# Stepper5.net
KiCad netlist of a schematic drawn in EAGLE
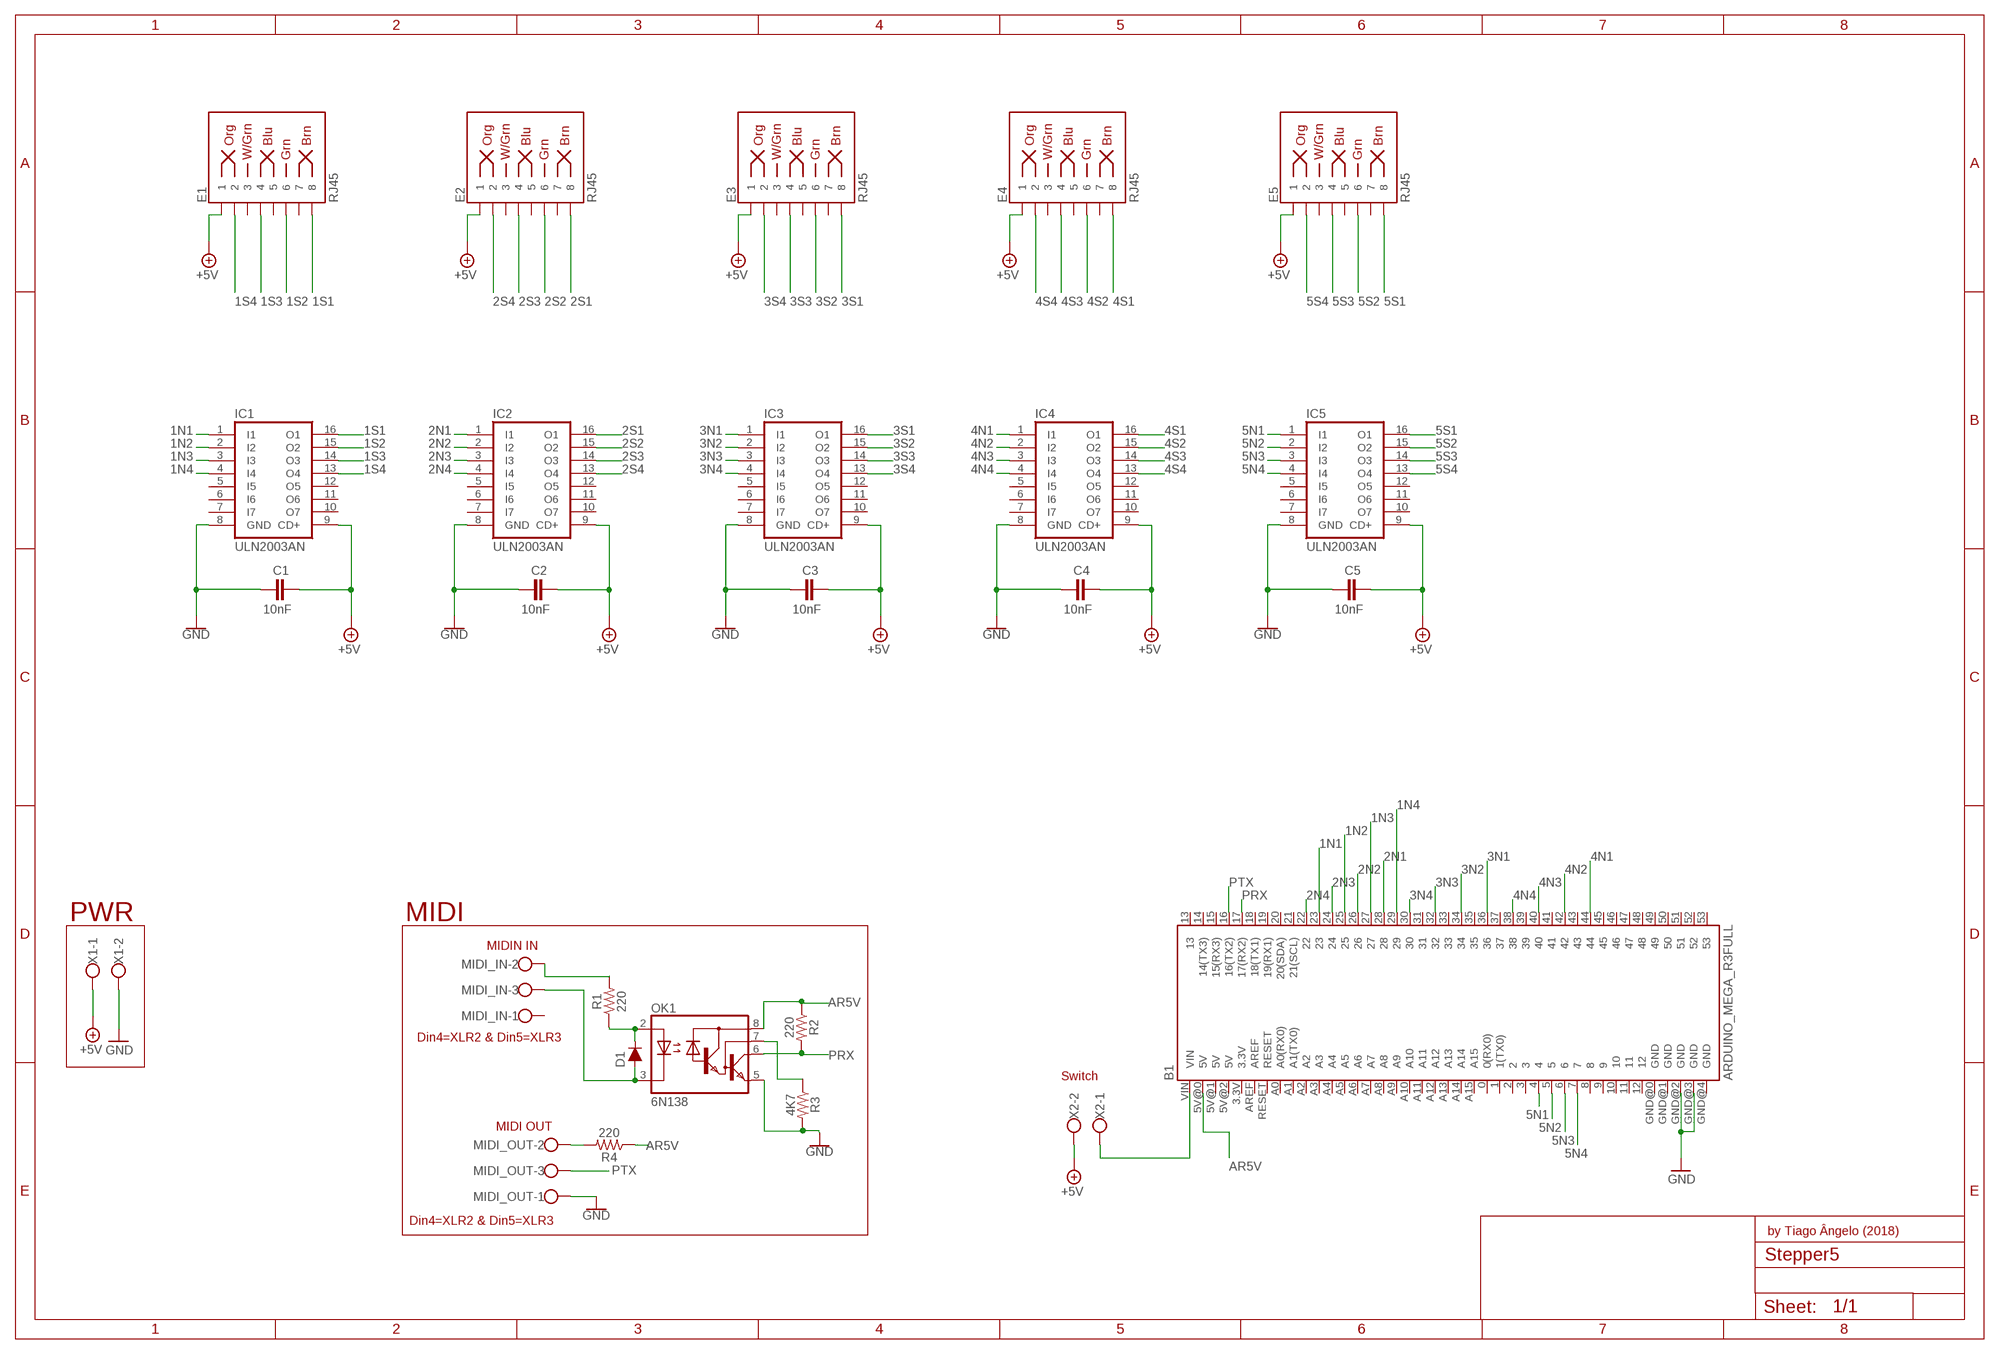
[diagram p0: schematic, sheet 1]

(export (version "E")
  (design (tool "Eeschema 10.0.6"))
  (components
    (comp (ref "B1")
      (value "ARDUINO_MEGA_R3FULL")
      (footprint "eagle-import:ARDUINO_MEGA")
      (libsource (lib "eagle-import") (part "ARDUINO_MEGA_R3FULL"))
    )
    (comp (ref "C1")
      (value "10nF")
      (footprint "eagle-import:C5B2.5")
      (libsource (lib "eagle-import") (part "C5/2.5"))
    )
    (comp (ref "C2")
      (value "10nF")
      (footprint "eagle-import:C5B2.5")
      (libsource (lib "eagle-import") (part "C5/2.5"))
    )
    (comp (ref "C3")
      (value "10nF")
      (footprint "eagle-import:C5B2.5")
      (libsource (lib "eagle-import") (part "C5/2.5"))
    )
    (comp (ref "C4")
      (value "10nF")
      (footprint "eagle-import:C5B2.5")
      (libsource (lib "eagle-import") (part "C5/2.5"))
    )
    (comp (ref "C5")
      (value "10nF")
      (footprint "eagle-import:C5B2.5")
      (libsource (lib "eagle-import") (part "C5/2.5"))
    )
    (comp (ref "D1")
      (value "200mA/100V/1V")
      (footprint "eagle-import:DIODE-1N4148")
      (libsource (lib "eagle-import") (part "DIODE-1N4148"))
    )
    (comp (ref "E1")
      (value "RJ45")
      (footprint "eagle-import:RJ45-8")
      (libsource (lib "eagle-import") (part "RJ45-8"))
    )
    (comp (ref "E2")
      (value "RJ45")
      (footprint "eagle-import:RJ45-8")
      (libsource (lib "eagle-import") (part "RJ45-8"))
    )
    (comp (ref "E3")
      (value "RJ45")
      (footprint "eagle-import:RJ45-8")
      (libsource (lib "eagle-import") (part "RJ45-8"))
    )
    (comp (ref "E4")
      (value "RJ45")
      (footprint "eagle-import:RJ45-8")
      (libsource (lib "eagle-import") (part "RJ45-8"))
    )
    (comp (ref "E5")
      (value "RJ45")
      (footprint "eagle-import:RJ45-8")
      (libsource (lib "eagle-import") (part "RJ45-8"))
    )
    (comp (ref "IC1")
      (value "ULN2003AN")
      (footprint "eagle-import:DIL16")
      (libsource (lib "eagle-import") (part "ULN2003AN"))
    )
    (comp (ref "IC2")
      (value "ULN2003AN")
      (footprint "eagle-import:DIL16")
      (libsource (lib "eagle-import") (part "ULN2003AN"))
    )
    (comp (ref "IC3")
      (value "ULN2003AN")
      (footprint "eagle-import:DIL16")
      (libsource (lib "eagle-import") (part "ULN2003AN"))
    )
    (comp (ref "IC4")
      (value "ULN2003AN")
      (footprint "eagle-import:DIL16")
      (libsource (lib "eagle-import") (part "ULN2003AN"))
    )
    (comp (ref "IC5")
      (value "ULN2003AN")
      (footprint "eagle-import:DIL16")
      (libsource (lib "eagle-import") (part "ULN2003AN"))
    )
    (comp (ref "MIDI_IN")
      (value "W237-103")
      (footprint "eagle-import:W237-103")
      (fields (field (name "MPN") "237-103"))
      (libsource (lib "eagle-import") (part "W237-103"))
    )
    (comp (ref "MIDI_OUT")
      (value "W237-103")
      (footprint "eagle-import:W237-103")
      (fields (field (name "MPN") "237-103"))
      (libsource (lib "eagle-import") (part "W237-103"))
    )
    (comp (ref "OK1")
      (value "6N138")
      (footprint "eagle-import:DIL08")
      (fields (field (name "MF") "VISHAY/TELEFUNKEN"))
      (libsource (lib "eagle-import") (part "6N138"))
    )
    (comp (ref "R1")
      (value "220")
      (footprint "eagle-import:AXIAL-0.3")
      (libsource (lib "eagle-import") (part "1KOHM-HORIZ-1/4W-5%"))
    )
    (comp (ref "R2")
      (value "220")
      (footprint "eagle-import:AXIAL-0.3")
      (libsource (lib "eagle-import") (part "1KOHM-HORIZ-1/4W-5%"))
    )
    (comp (ref "R3")
      (value "4K7")
      (footprint "eagle-import:AXIAL-0.3")
      (libsource (lib "eagle-import") (part "1KOHM-HORIZ-1/4W-5%"))
    )
    (comp (ref "R4")
      (value "220")
      (footprint "eagle-import:AXIAL-0.3")
      (libsource (lib "eagle-import") (part "1KOHM-HORIZ-1/4W-5%"))
    )
    (comp (ref "X1")
      (value "W237-102")
      (footprint "eagle-import:W237-102")
      (fields (field (name "MPN") "237-102"))
      (libsource (lib "eagle-import") (part "W237-102"))
    )
    (comp (ref "X2")
      (value "W237-102")
      (footprint "eagle-import:W237-102")
      (fields (field (name "MPN") "237-102"))
      (libsource (lib "eagle-import") (part "W237-102"))
    )
  )
  (nets
    (net (code "1") (name "+5V") (class "Default")
      (node (ref "C1") (pin "2") (pinfunction "2_2") (pintype "passive"))
      (node (ref "C2") (pin "2") (pinfunction "2_2") (pintype "passive"))
      (node (ref "C3") (pin "2") (pinfunction "2_2") (pintype "passive"))
      (node (ref "C4") (pin "2") (pinfunction "2_2") (pintype "passive"))
      (node (ref "C5") (pin "2") (pinfunction "2_2") (pintype "passive"))
      (node (ref "E1") (pin "1") (pinfunction "1_1") (pintype "bidirectional"))
      (node (ref "E2") (pin "1") (pinfunction "1_1") (pintype "bidirectional"))
      (node (ref "E3") (pin "1") (pinfunction "1_1") (pintype "bidirectional"))
      (node (ref "E4") (pin "1") (pinfunction "1_1") (pintype "bidirectional"))
      (node (ref "E5") (pin "1") (pinfunction "1_1") (pintype "bidirectional"))
      (node (ref "IC1") (pin "9") (pinfunction "CD+_9") (pintype "passive"))
      (node (ref "IC2") (pin "9") (pinfunction "CD+_9") (pintype "passive"))
      (node (ref "IC3") (pin "9") (pinfunction "CD+_9") (pintype "passive"))
      (node (ref "IC4") (pin "9") (pinfunction "CD+_9") (pintype "passive"))
      (node (ref "IC5") (pin "9") (pinfunction "CD+_9") (pintype "passive"))
      (node (ref "X1") (pin "1") (pinfunction "KL_1") (pintype "passive"))
      (node (ref "X2") (pin "2") (pinfunction "KL_2") (pintype "passive"))
    )
    (net (code "2") (name "/1N1") (class "Default")
      (node (ref "B1") (pin "23") (pinfunction "23_23") (pintype "bidirectional"))
      (node (ref "IC1") (pin "1") (pinfunction "I1_1") (pintype "input"))
    )
    (net (code "3") (name "/1N2") (class "Default")
      (node (ref "B1") (pin "25") (pinfunction "25_25") (pintype "bidirectional"))
      (node (ref "IC1") (pin "2") (pinfunction "I2_2") (pintype "input"))
    )
    (net (code "4") (name "/1N3") (class "Default")
      (node (ref "B1") (pin "27") (pinfunction "27_27") (pintype "bidirectional"))
      (node (ref "IC1") (pin "3") (pinfunction "I3_3") (pintype "input"))
    )
    (net (code "5") (name "/1N4") (class "Default")
      (node (ref "B1") (pin "29") (pinfunction "29_29") (pintype "bidirectional"))
      (node (ref "IC1") (pin "4") (pinfunction "I4_4") (pintype "input"))
    )
    (net (code "6") (name "/1S1") (class "Default")
      (node (ref "E1") (pin "8") (pinfunction "8_8") (pintype "bidirectional"))
      (node (ref "IC1") (pin "16") (pinfunction "O1_16") (pintype "open_collector"))
    )
    (net (code "7") (name "/1S2") (class "Default")
      (node (ref "E1") (pin "6") (pinfunction "6_6") (pintype "bidirectional"))
      (node (ref "IC1") (pin "15") (pinfunction "O2_15") (pintype "open_collector"))
    )
    (net (code "8") (name "/1S3") (class "Default")
      (node (ref "E1") (pin "4") (pinfunction "4_4") (pintype "bidirectional"))
      (node (ref "IC1") (pin "14") (pinfunction "O3_14") (pintype "open_collector"))
    )
    (net (code "9") (name "/1S4") (class "Default")
      (node (ref "E1") (pin "2") (pinfunction "2_2") (pintype "bidirectional"))
      (node (ref "IC1") (pin "13") (pinfunction "O4_13") (pintype "open_collector"))
    )
    (net (code "10") (name "/2N1") (class "Default")
      (node (ref "B1") (pin "28") (pinfunction "28_28") (pintype "bidirectional"))
      (node (ref "IC2") (pin "1") (pinfunction "I1_1") (pintype "input"))
    )
    (net (code "11") (name "/2N2") (class "Default")
      (node (ref "B1") (pin "26") (pinfunction "26_26") (pintype "bidirectional"))
      (node (ref "IC2") (pin "2") (pinfunction "I2_2") (pintype "input"))
    )
    (net (code "12") (name "/2N3") (class "Default")
      (node (ref "B1") (pin "24") (pinfunction "24_24") (pintype "bidirectional"))
      (node (ref "IC2") (pin "3") (pinfunction "I3_3") (pintype "input"))
    )
    (net (code "13") (name "/2N4") (class "Default")
      (node (ref "B1") (pin "22") (pinfunction "22_22") (pintype "bidirectional"))
      (node (ref "IC2") (pin "4") (pinfunction "I4_4") (pintype "input"))
    )
    (net (code "14") (name "/2S1") (class "Default")
      (node (ref "E2") (pin "8") (pinfunction "8_8") (pintype "bidirectional"))
      (node (ref "IC2") (pin "16") (pinfunction "O1_16") (pintype "open_collector"))
    )
    (net (code "15") (name "/2S2") (class "Default")
      (node (ref "E2") (pin "6") (pinfunction "6_6") (pintype "bidirectional"))
      (node (ref "IC2") (pin "15") (pinfunction "O2_15") (pintype "open_collector"))
    )
    (net (code "16") (name "/2S3") (class "Default")
      (node (ref "E2") (pin "4") (pinfunction "4_4") (pintype "bidirectional"))
      (node (ref "IC2") (pin "14") (pinfunction "O3_14") (pintype "open_collector"))
    )
    (net (code "17") (name "/2S4") (class "Default")
      (node (ref "E2") (pin "2") (pinfunction "2_2") (pintype "bidirectional"))
      (node (ref "IC2") (pin "13") (pinfunction "O4_13") (pintype "open_collector"))
    )
    (net (code "18") (name "/3N1") (class "Default")
      (node (ref "B1") (pin "36") (pinfunction "36_36") (pintype "bidirectional"))
      (node (ref "IC3") (pin "1") (pinfunction "I1_1") (pintype "input"))
    )
    (net (code "19") (name "/3N2") (class "Default")
      (node (ref "B1") (pin "34") (pinfunction "34_34") (pintype "bidirectional"))
      (node (ref "IC3") (pin "2") (pinfunction "I2_2") (pintype "input"))
    )
    (net (code "20") (name "/3N3") (class "Default")
      (node (ref "B1") (pin "32") (pinfunction "32_32") (pintype "bidirectional"))
      (node (ref "IC3") (pin "3") (pinfunction "I3_3") (pintype "input"))
    )
    (net (code "21") (name "/3N4") (class "Default")
      (node (ref "B1") (pin "30") (pinfunction "30_30") (pintype "bidirectional"))
      (node (ref "IC3") (pin "4") (pinfunction "I4_4") (pintype "input"))
    )
    (net (code "22") (name "/3S1") (class "Default")
      (node (ref "E3") (pin "8") (pinfunction "8_8") (pintype "bidirectional"))
      (node (ref "IC3") (pin "16") (pinfunction "O1_16") (pintype "open_collector"))
    )
    (net (code "23") (name "/3S2") (class "Default")
      (node (ref "E3") (pin "6") (pinfunction "6_6") (pintype "bidirectional"))
      (node (ref "IC3") (pin "15") (pinfunction "O2_15") (pintype "open_collector"))
    )
    (net (code "24") (name "/3S3") (class "Default")
      (node (ref "E3") (pin "4") (pinfunction "4_4") (pintype "bidirectional"))
      (node (ref "IC3") (pin "14") (pinfunction "O3_14") (pintype "open_collector"))
    )
    (net (code "25") (name "/3S4") (class "Default")
      (node (ref "E3") (pin "2") (pinfunction "2_2") (pintype "bidirectional"))
      (node (ref "IC3") (pin "13") (pinfunction "O4_13") (pintype "open_collector"))
    )
    (net (code "26") (name "/4N1") (class "Default")
      (node (ref "B1") (pin "44") (pinfunction "44_44") (pintype "bidirectional"))
      (node (ref "IC4") (pin "1") (pinfunction "I1_1") (pintype "input"))
    )
    (net (code "27") (name "/4N2") (class "Default")
      (node (ref "B1") (pin "42") (pinfunction "42_42") (pintype "bidirectional"))
      (node (ref "IC4") (pin "2") (pinfunction "I2_2") (pintype "input"))
    )
    (net (code "28") (name "/4N3") (class "Default")
      (node (ref "B1") (pin "40") (pinfunction "40_40") (pintype "bidirectional"))
      (node (ref "IC4") (pin "3") (pinfunction "I3_3") (pintype "input"))
    )
    (net (code "29") (name "/4N4") (class "Default")
      (node (ref "B1") (pin "38") (pinfunction "38_38") (pintype "bidirectional"))
      (node (ref "IC4") (pin "4") (pinfunction "I4_4") (pintype "input"))
    )
    (net (code "30") (name "/4S1") (class "Default")
      (node (ref "E4") (pin "8") (pinfunction "8_8") (pintype "bidirectional"))
      (node (ref "IC4") (pin "16") (pinfunction "O1_16") (pintype "open_collector"))
    )
    (net (code "31") (name "/4S2") (class "Default")
      (node (ref "E4") (pin "6") (pinfunction "6_6") (pintype "bidirectional"))
      (node (ref "IC4") (pin "15") (pinfunction "O2_15") (pintype "open_collector"))
    )
    (net (code "32") (name "/4S3") (class "Default")
      (node (ref "E4") (pin "4") (pinfunction "4_4") (pintype "bidirectional"))
      (node (ref "IC4") (pin "14") (pinfunction "O3_14") (pintype "open_collector"))
    )
    (net (code "33") (name "/4S4") (class "Default")
      (node (ref "E4") (pin "2") (pinfunction "2_2") (pintype "bidirectional"))
      (node (ref "IC4") (pin "13") (pinfunction "O4_13") (pintype "open_collector"))
    )
    (net (code "34") (name "/5N1") (class "Default")
      (node (ref "B1") (pin "4") (pinfunction "4_4") (pintype "bidirectional"))
      (node (ref "IC5") (pin "1") (pinfunction "I1_1") (pintype "input"))
    )
    (net (code "35") (name "/5N2") (class "Default")
      (node (ref "B1") (pin "5") (pinfunction "5_5") (pintype "bidirectional"))
      (node (ref "IC5") (pin "2") (pinfunction "I2_2") (pintype "input"))
    )
    (net (code "36") (name "/5N3") (class "Default")
      (node (ref "B1") (pin "6") (pinfunction "6_6") (pintype "bidirectional"))
      (node (ref "IC5") (pin "3") (pinfunction "I3_3") (pintype "input"))
    )
    (net (code "37") (name "/5N4") (class "Default")
      (node (ref "B1") (pin "7") (pinfunction "7_7") (pintype "bidirectional"))
      (node (ref "IC5") (pin "4") (pinfunction "I4_4") (pintype "input"))
    )
    (net (code "38") (name "/5S1") (class "Default")
      (node (ref "E5") (pin "8") (pinfunction "8_8") (pintype "bidirectional"))
      (node (ref "IC5") (pin "16") (pinfunction "O1_16") (pintype "open_collector"))
    )
    (net (code "39") (name "/5S2") (class "Default")
      (node (ref "E5") (pin "6") (pinfunction "6_6") (pintype "bidirectional"))
      (node (ref "IC5") (pin "15") (pinfunction "O2_15") (pintype "open_collector"))
    )
    (net (code "40") (name "/5S3") (class "Default")
      (node (ref "E5") (pin "4") (pinfunction "4_4") (pintype "bidirectional"))
      (node (ref "IC5") (pin "14") (pinfunction "O3_14") (pintype "open_collector"))
    )
    (net (code "41") (name "/5S4") (class "Default")
      (node (ref "E5") (pin "2") (pinfunction "2_2") (pintype "bidirectional"))
      (node (ref "IC5") (pin "13") (pinfunction "O4_13") (pintype "open_collector"))
    )
    (net (code "42") (name "/AR5V") (class "Default")
      (node (ref "B1") (pin "5V@0") (pinfunction "5V_5V@0") (pintype "bidirectional"))
      (node (ref "OK1") (pin "8") (pinfunction "VCC_8") (pintype "passive"))
      (node (ref "R2") (pin "P$1") (pinfunction "1_P$1") (pintype "passive"))
      (node (ref "R4") (pin "P$1") (pinfunction "1_P$1") (pintype "passive"))
    )
    (net (code "43") (name "/PRX") (class "Default")
      (node (ref "B1") (pin "17") (pinfunction "17(RX2)_17") (pintype "bidirectional"))
      (node (ref "OK1") (pin "6") (pinfunction "VO_6") (pintype "passive"))
      (node (ref "R2") (pin "P$2") (pinfunction "2_P$2") (pintype "passive"))
    )
    (net (code "44") (name "/PTX") (class "Default")
      (node (ref "B1") (pin "16") (pinfunction "16(TX2)_16") (pintype "bidirectional"))
      (node (ref "MIDI_OUT") (pin "3") (pinfunction "KL_3") (pintype "passive"))
    )
    (net (code "45") (name "GND") (class "Default")
      (node (ref "B1") (pin "GND@2") (pinfunction "GND_GND@2") (pintype "bidirectional"))
      (node (ref "B1") (pin "GND@3") (pinfunction "GND_GND@3") (pintype "bidirectional"))
      (node (ref "C1") (pin "1") (pinfunction "1_1") (pintype "passive"))
      (node (ref "C2") (pin "1") (pinfunction "1_1") (pintype "passive"))
      (node (ref "C3") (pin "1") (pinfunction "1_1") (pintype "passive"))
      (node (ref "C4") (pin "1") (pinfunction "1_1") (pintype "passive"))
      (node (ref "C5") (pin "1") (pinfunction "1_1") (pintype "passive"))
      (node (ref "IC1") (pin "8") (pinfunction "GND_8") (pintype "power_in"))
      (node (ref "IC2") (pin "8") (pinfunction "GND_8") (pintype "power_in"))
      (node (ref "IC3") (pin "8") (pinfunction "GND_8") (pintype "power_in"))
      (node (ref "IC4") (pin "8") (pinfunction "GND_8") (pintype "power_in"))
      (node (ref "IC5") (pin "8") (pinfunction "GND_8") (pintype "power_in"))
      (node (ref "MIDI_OUT") (pin "1") (pinfunction "KL_1") (pintype "passive"))
      (node (ref "OK1") (pin "5") (pinfunction "GND_5") (pintype "passive"))
      (node (ref "R3") (pin "P$2") (pinfunction "2_P$2") (pintype "passive"))
      (node (ref "X1") (pin "2") (pinfunction "KL_2") (pintype "passive"))
    )
    (net (code "46") (name "Net-(MIDI_INB-KL)") (class "Default")
      (node (ref "MIDI_IN") (pin "2") (pinfunction "KL_2") (pintype "passive"))
      (node (ref "R1") (pin "P$2") (pinfunction "2_P$2") (pintype "passive"))
    )
    (net (code "47") (name "Net-(MIDI_INC-KL)") (class "Default")
      (node (ref "D1") (pin "A") (pinfunction "A_A") (pintype "passive"))
      (node (ref "MIDI_IN") (pin "3") (pinfunction "KL_3") (pintype "passive"))
      (node (ref "OK1") (pin "3") (pinfunction "C_3") (pintype "passive"))
    )
    (net (code "48") (name "Net-(MIDI_OUTB-KL)") (class "Default")
      (node (ref "MIDI_OUT") (pin "2") (pinfunction "KL_2") (pintype "passive"))
      (node (ref "R4") (pin "P$2") (pinfunction "2_P$2") (pintype "passive"))
    )
    (net (code "49") (name "Net-(OK1-A)") (class "Default")
      (node (ref "D1") (pin "C") (pinfunction "C_C") (pintype "passive"))
      (node (ref "OK1") (pin "2") (pinfunction "A_2") (pintype "passive"))
      (node (ref "R1") (pin "P$1") (pinfunction "1_P$1") (pintype "passive"))
    )
    (net (code "50") (name "Net-(OK1-VB)") (class "Default")
      (node (ref "OK1") (pin "7") (pinfunction "VB_7") (pintype "passive"))
      (node (ref "R3") (pin "P$1") (pinfunction "1_P$1") (pintype "passive"))
    )
    (net (code "51") (name "Net-(X2A-KL)") (class "Default")
      (node (ref "B1") (pin "VIN") (pinfunction "VIN_VIN") (pintype "bidirectional"))
      (node (ref "X2") (pin "1") (pinfunction "KL_1") (pintype "passive"))
    )
    (net (code "52") (name "unconnected-(B1-0(RX0)-Pad0)") (class "Default")
      (node (ref "B1") (pin "0") (pinfunction "0(RX0)_0") (pintype "bidirectional"))
    )
    (net (code "53") (name "unconnected-(B1-1(TX0)-Pad1)") (class "Default")
      (node (ref "B1") (pin "1") (pinfunction "1(TX0)_1") (pintype "bidirectional"))
    )
    (net (code "54") (name "unconnected-(B1-5V-Pad5V@1)") (class "Default")
      (node (ref "B1") (pin "5V@1") (pinfunction "5V_5V@1") (pintype "bidirectional"))
    )
    (net (code "55") (name "unconnected-(B1-5V-Pad5V@2)") (class "Default")
      (node (ref "B1") (pin "5V@2") (pinfunction "5V_5V@2") (pintype "bidirectional"))
    )
    (net (code "56") (name "unconnected-(B1-14(TX3)-Pad14)") (class "Default")
      (node (ref "B1") (pin "14") (pinfunction "14(TX3)_14") (pintype "bidirectional"))
    )
    (net (code "57") (name "unconnected-(B1-15(RX3)-Pad15)") (class "Default")
      (node (ref "B1") (pin "15") (pinfunction "15(RX3)_15") (pintype "bidirectional"))
    )
    (net (code "58") (name "unconnected-(B1-18(TX1)-Pad18)") (class "Default")
      (node (ref "B1") (pin "18") (pinfunction "18(TX1)_18") (pintype "bidirectional"))
    )
    (net (code "59") (name "unconnected-(B1-19(RX1)-Pad19)") (class "Default")
      (node (ref "B1") (pin "19") (pinfunction "19(RX1)_19") (pintype "bidirectional"))
    )
    (net (code "60") (name "unconnected-(B1-20(SDA)-Pad20)") (class "Default")
      (node (ref "B1") (pin "20") (pinfunction "20(SDA)_20") (pintype "bidirectional"))
    )
    (net (code "61") (name "unconnected-(B1-21(SCL)-Pad21)") (class "Default")
      (node (ref "B1") (pin "21") (pinfunction "21(SCL)_21") (pintype "bidirectional"))
    )
    (net (code "62") (name "unconnected-(B1-A0(RX0)-PadA0)") (class "Default")
      (node (ref "B1") (pin "A0") (pinfunction "A0(RX0)_A0") (pintype "bidirectional"))
    )
    (net (code "63") (name "unconnected-(B1-A1(TX0)-PadA1)") (class "Default")
      (node (ref "B1") (pin "A1") (pinfunction "A1(TX0)_A1") (pintype "bidirectional"))
    )
    (net (code "64") (name "unconnected-(B1-GND-PadGND@0)") (class "Default")
      (node (ref "B1") (pin "GND@0") (pinfunction "GND_GND@0") (pintype "bidirectional"))
    )
    (net (code "65") (name "unconnected-(B1-GND-PadGND@1)") (class "Default")
      (node (ref "B1") (pin "GND@1") (pinfunction "GND_GND@1") (pintype "bidirectional"))
    )
    (net (code "66") (name "unconnected-(B1-GND-PadGND@4)") (class "Default")
      (node (ref "B1") (pin "GND@4") (pinfunction "GND_GND@4") (pintype "bidirectional"))
    )
    (net (code "67") (name "unconnected-(B1-Pad2)") (class "Default")
      (node (ref "B1") (pin "2") (pinfunction "2_2") (pintype "bidirectional"))
    )
    (net (code "68") (name "unconnected-(B1-Pad3)") (class "Default")
      (node (ref "B1") (pin "3") (pinfunction "3_3") (pintype "bidirectional"))
    )
    (net (code "69") (name "unconnected-(B1-Pad3.3V)") (class "Default")
      (node (ref "B1") (pin "3.3V") (pinfunction "3.3V_3.3V") (pintype "bidirectional"))
    )
    (net (code "70") (name "unconnected-(B1-Pad8)") (class "Default")
      (node (ref "B1") (pin "8") (pinfunction "8_8") (pintype "bidirectional"))
    )
    (net (code "71") (name "unconnected-(B1-Pad9)") (class "Default")
      (node (ref "B1") (pin "9") (pinfunction "9_9") (pintype "bidirectional"))
    )
    (net (code "72") (name "unconnected-(B1-Pad10)") (class "Default")
      (node (ref "B1") (pin "10") (pinfunction "10_10") (pintype "bidirectional"))
    )
    (net (code "73") (name "unconnected-(B1-Pad11)") (class "Default")
      (node (ref "B1") (pin "11") (pinfunction "11_11") (pintype "bidirectional"))
    )
    (net (code "74") (name "unconnected-(B1-Pad12)") (class "Default")
      (node (ref "B1") (pin "12") (pinfunction "12_12") (pintype "bidirectional"))
    )
    (net (code "75") (name "unconnected-(B1-Pad13)") (class "Default")
      (node (ref "B1") (pin "13") (pinfunction "13_13") (pintype "bidirectional"))
    )
    (net (code "76") (name "unconnected-(B1-Pad31)") (class "Default")
      (node (ref "B1") (pin "31") (pinfunction "31_31") (pintype "bidirectional"))
    )
    (net (code "77") (name "unconnected-(B1-Pad33)") (class "Default")
      (node (ref "B1") (pin "33") (pinfunction "33_33") (pintype "bidirectional"))
    )
    (net (code "78") (name "unconnected-(B1-Pad35)") (class "Default")
      (node (ref "B1") (pin "35") (pinfunction "35_35") (pintype "bidirectional"))
    )
    (net (code "79") (name "unconnected-(B1-Pad37)") (class "Default")
      (node (ref "B1") (pin "37") (pinfunction "37_37") (pintype "bidirectional"))
    )
    (net (code "80") (name "unconnected-(B1-Pad39)") (class "Default")
      (node (ref "B1") (pin "39") (pinfunction "39_39") (pintype "bidirectional"))
    )
    (net (code "81") (name "unconnected-(B1-Pad41)") (class "Default")
      (node (ref "B1") (pin "41") (pinfunction "41_41") (pintype "bidirectional"))
    )
    (net (code "82") (name "unconnected-(B1-Pad43)") (class "Default")
      (node (ref "B1") (pin "43") (pinfunction "43_43") (pintype "bidirectional"))
    )
    (net (code "83") (name "unconnected-(B1-Pad45)") (class "Default")
      (node (ref "B1") (pin "45") (pinfunction "45_45") (pintype "bidirectional"))
    )
    (net (code "84") (name "unconnected-(B1-Pad46)") (class "Default")
      (node (ref "B1") (pin "46") (pinfunction "46_46") (pintype "bidirectional"))
    )
    (net (code "85") (name "unconnected-(B1-Pad47)") (class "Default")
      (node (ref "B1") (pin "47") (pinfunction "47_47") (pintype "bidirectional"))
    )
    (net (code "86") (name "unconnected-(B1-Pad48)") (class "Default")
      (node (ref "B1") (pin "48") (pinfunction "48_48") (pintype "bidirectional"))
    )
    (net (code "87") (name "unconnected-(B1-Pad49)") (class "Default")
      (node (ref "B1") (pin "49") (pinfunction "49_49") (pintype "bidirectional"))
    )
    (net (code "88") (name "unconnected-(B1-Pad50)") (class "Default")
      (node (ref "B1") (pin "50") (pinfunction "50_50") (pintype "bidirectional"))
    )
    (net (code "89") (name "unconnected-(B1-Pad51)") (class "Default")
      (node (ref "B1") (pin "51") (pinfunction "51_51") (pintype "bidirectional"))
    )
    (net (code "90") (name "unconnected-(B1-Pad52)") (class "Default")
      (node (ref "B1") (pin "52") (pinfunction "52_52") (pintype "bidirectional"))
    )
    (net (code "91") (name "unconnected-(B1-Pad53)") (class "Default")
      (node (ref "B1") (pin "53") (pinfunction "53_53") (pintype "bidirectional"))
    )
    (net (code "92") (name "unconnected-(B1-PadA2)") (class "Default")
      (node (ref "B1") (pin "A2") (pinfunction "A2_A2") (pintype "bidirectional"))
    )
    (net (code "93") (name "unconnected-(B1-PadA3)") (class "Default")
      (node (ref "B1") (pin "A3") (pinfunction "A3_A3") (pintype "bidirectional"))
    )
    (net (code "94") (name "unconnected-(B1-PadA4)") (class "Default")
      (node (ref "B1") (pin "A4") (pinfunction "A4_A4") (pintype "bidirectional"))
    )
    (net (code "95") (name "unconnected-(B1-PadA5)") (class "Default")
      (node (ref "B1") (pin "A5") (pinfunction "A5_A5") (pintype "bidirectional"))
    )
    (net (code "96") (name "unconnected-(B1-PadA6)") (class "Default")
      (node (ref "B1") (pin "A6") (pinfunction "A6_A6") (pintype "bidirectional"))
    )
    (net (code "97") (name "unconnected-(B1-PadA7)") (class "Default")
      (node (ref "B1") (pin "A7") (pinfunction "A7_A7") (pintype "bidirectional"))
    )
    (net (code "98") (name "unconnected-(B1-PadA8)") (class "Default")
      (node (ref "B1") (pin "A8") (pinfunction "A8_A8") (pintype "bidirectional"))
    )
    (net (code "99") (name "unconnected-(B1-PadA9)") (class "Default")
      (node (ref "B1") (pin "A9") (pinfunction "A9_A9") (pintype "bidirectional"))
    )
    (net (code "100") (name "unconnected-(B1-PadA10)") (class "Default")
      (node (ref "B1") (pin "A10") (pinfunction "A10_A10") (pintype "bidirectional"))
    )
    (net (code "101") (name "unconnected-(B1-PadA11)") (class "Default")
      (node (ref "B1") (pin "A11") (pinfunction "A11_A11") (pintype "bidirectional"))
    )
    (net (code "102") (name "unconnected-(B1-PadA12)") (class "Default")
      (node (ref "B1") (pin "A12") (pinfunction "A12_A12") (pintype "bidirectional"))
    )
    (net (code "103") (name "unconnected-(B1-PadA13)") (class "Default")
      (node (ref "B1") (pin "A13") (pinfunction "A13_A13") (pintype "bidirectional"))
    )
    (net (code "104") (name "unconnected-(B1-PadA14)") (class "Default")
      (node (ref "B1") (pin "A14") (pinfunction "A14_A14") (pintype "bidirectional"))
    )
    (net (code "105") (name "unconnected-(B1-PadA15)") (class "Default")
      (node (ref "B1") (pin "A15") (pinfunction "A15_A15") (pintype "bidirectional"))
    )
    (net (code "106") (name "unconnected-(B1-PadAREF)") (class "Default")
      (node (ref "B1") (pin "AREF") (pinfunction "AREF_AREF") (pintype "bidirectional"))
    )
    (net (code "107") (name "unconnected-(B1-PadRESET)") (class "Default")
      (node (ref "B1") (pin "RESET") (pinfunction "RESET_RESET") (pintype "bidirectional"))
    )
    (net (code "108") (name "unconnected-(E1-Pad3)") (class "Default")
      (node (ref "E1") (pin "3") (pinfunction "3_3") (pintype "bidirectional"))
    )
    (net (code "109") (name "unconnected-(E1-Pad5)") (class "Default")
      (node (ref "E1") (pin "5") (pinfunction "5_5") (pintype "bidirectional"))
    )
    (net (code "110") (name "unconnected-(E1-Pad7)") (class "Default")
      (node (ref "E1") (pin "7") (pinfunction "7_7") (pintype "bidirectional"))
    )
    (net (code "111") (name "unconnected-(E2-Pad3)") (class "Default")
      (node (ref "E2") (pin "3") (pinfunction "3_3") (pintype "bidirectional"))
    )
    (net (code "112") (name "unconnected-(E2-Pad5)") (class "Default")
      (node (ref "E2") (pin "5") (pinfunction "5_5") (pintype "bidirectional"))
    )
    (net (code "113") (name "unconnected-(E2-Pad7)") (class "Default")
      (node (ref "E2") (pin "7") (pinfunction "7_7") (pintype "bidirectional"))
    )
    (net (code "114") (name "unconnected-(E3-Pad3)") (class "Default")
      (node (ref "E3") (pin "3") (pinfunction "3_3") (pintype "bidirectional"))
    )
    (net (code "115") (name "unconnected-(E3-Pad5)") (class "Default")
      (node (ref "E3") (pin "5") (pinfunction "5_5") (pintype "bidirectional"))
    )
    (net (code "116") (name "unconnected-(E3-Pad7)") (class "Default")
      (node (ref "E3") (pin "7") (pinfunction "7_7") (pintype "bidirectional"))
    )
    (net (code "117") (name "unconnected-(E4-Pad3)") (class "Default")
      (node (ref "E4") (pin "3") (pinfunction "3_3") (pintype "bidirectional"))
    )
    (net (code "118") (name "unconnected-(E4-Pad5)") (class "Default")
      (node (ref "E4") (pin "5") (pinfunction "5_5") (pintype "bidirectional"))
    )
    (net (code "119") (name "unconnected-(E4-Pad7)") (class "Default")
      (node (ref "E4") (pin "7") (pinfunction "7_7") (pintype "bidirectional"))
    )
    (net (code "120") (name "unconnected-(E5-Pad3)") (class "Default")
      (node (ref "E5") (pin "3") (pinfunction "3_3") (pintype "bidirectional"))
    )
    (net (code "121") (name "unconnected-(E5-Pad5)") (class "Default")
      (node (ref "E5") (pin "5") (pinfunction "5_5") (pintype "bidirectional"))
    )
    (net (code "122") (name "unconnected-(E5-Pad7)") (class "Default")
      (node (ref "E5") (pin "7") (pinfunction "7_7") (pintype "bidirectional"))
    )
    (net (code "123") (name "unconnected-(IC1-I5-Pad5)") (class "Default")
      (node (ref "IC1") (pin "5") (pinfunction "I5_5") (pintype "input"))
    )
    (net (code "124") (name "unconnected-(IC1-I6-Pad6)") (class "Default")
      (node (ref "IC1") (pin "6") (pinfunction "I6_6") (pintype "input"))
    )
    (net (code "125") (name "unconnected-(IC1-I7-Pad7)") (class "Default")
      (node (ref "IC1") (pin "7") (pinfunction "I7_7") (pintype "input"))
    )
    (net (code "126") (name "unconnected-(IC1-O5-Pad12)") (class "Default")
      (node (ref "IC1") (pin "12") (pinfunction "O5_12") (pintype "open_collector"))
    )
    (net (code "127") (name "unconnected-(IC1-O6-Pad11)") (class "Default")
      (node (ref "IC1") (pin "11") (pinfunction "O6_11") (pintype "open_collector"))
    )
    (net (code "128") (name "unconnected-(IC1-O7-Pad10)") (class "Default")
      (node (ref "IC1") (pin "10") (pinfunction "O7_10") (pintype "open_collector"))
    )
    (net (code "129") (name "unconnected-(IC2-I5-Pad5)") (class "Default")
      (node (ref "IC2") (pin "5") (pinfunction "I5_5") (pintype "input"))
    )
    (net (code "130") (name "unconnected-(IC2-I6-Pad6)") (class "Default")
      (node (ref "IC2") (pin "6") (pinfunction "I6_6") (pintype "input"))
    )
    (net (code "131") (name "unconnected-(IC2-I7-Pad7)") (class "Default")
      (node (ref "IC2") (pin "7") (pinfunction "I7_7") (pintype "input"))
    )
    (net (code "132") (name "unconnected-(IC2-O5-Pad12)") (class "Default")
      (node (ref "IC2") (pin "12") (pinfunction "O5_12") (pintype "open_collector"))
    )
    (net (code "133") (name "unconnected-(IC2-O6-Pad11)") (class "Default")
      (node (ref "IC2") (pin "11") (pinfunction "O6_11") (pintype "open_collector"))
    )
    (net (code "134") (name "unconnected-(IC2-O7-Pad10)") (class "Default")
      (node (ref "IC2") (pin "10") (pinfunction "O7_10") (pintype "open_collector"))
    )
    (net (code "135") (name "unconnected-(IC3-I5-Pad5)") (class "Default")
      (node (ref "IC3") (pin "5") (pinfunction "I5_5") (pintype "input"))
    )
    (net (code "136") (name "unconnected-(IC3-I6-Pad6)") (class "Default")
      (node (ref "IC3") (pin "6") (pinfunction "I6_6") (pintype "input"))
    )
    (net (code "137") (name "unconnected-(IC3-I7-Pad7)") (class "Default")
      (node (ref "IC3") (pin "7") (pinfunction "I7_7") (pintype "input"))
    )
    (net (code "138") (name "unconnected-(IC3-O5-Pad12)") (class "Default")
      (node (ref "IC3") (pin "12") (pinfunction "O5_12") (pintype "open_collector"))
    )
    (net (code "139") (name "unconnected-(IC3-O6-Pad11)") (class "Default")
      (node (ref "IC3") (pin "11") (pinfunction "O6_11") (pintype "open_collector"))
    )
    (net (code "140") (name "unconnected-(IC3-O7-Pad10)") (class "Default")
      (node (ref "IC3") (pin "10") (pinfunction "O7_10") (pintype "open_collector"))
    )
    (net (code "141") (name "unconnected-(IC4-I5-Pad5)") (class "Default")
      (node (ref "IC4") (pin "5") (pinfunction "I5_5") (pintype "input"))
    )
    (net (code "142") (name "unconnected-(IC4-I6-Pad6)") (class "Default")
      (node (ref "IC4") (pin "6") (pinfunction "I6_6") (pintype "input"))
    )
    (net (code "143") (name "unconnected-(IC4-I7-Pad7)") (class "Default")
      (node (ref "IC4") (pin "7") (pinfunction "I7_7") (pintype "input"))
    )
    (net (code "144") (name "unconnected-(IC4-O5-Pad12)") (class "Default")
      (node (ref "IC4") (pin "12") (pinfunction "O5_12") (pintype "open_collector"))
    )
    (net (code "145") (name "unconnected-(IC4-O6-Pad11)") (class "Default")
      (node (ref "IC4") (pin "11") (pinfunction "O6_11") (pintype "open_collector"))
    )
    (net (code "146") (name "unconnected-(IC4-O7-Pad10)") (class "Default")
      (node (ref "IC4") (pin "10") (pinfunction "O7_10") (pintype "open_collector"))
    )
    (net (code "147") (name "unconnected-(IC5-I5-Pad5)") (class "Default")
      (node (ref "IC5") (pin "5") (pinfunction "I5_5") (pintype "input"))
    )
    (net (code "148") (name "unconnected-(IC5-I6-Pad6)") (class "Default")
      (node (ref "IC5") (pin "6") (pinfunction "I6_6") (pintype "input"))
    )
    (net (code "149") (name "unconnected-(IC5-I7-Pad7)") (class "Default")
      (node (ref "IC5") (pin "7") (pinfunction "I7_7") (pintype "input"))
    )
    (net (code "150") (name "unconnected-(IC5-O5-Pad12)") (class "Default")
      (node (ref "IC5") (pin "12") (pinfunction "O5_12") (pintype "open_collector"))
    )
    (net (code "151") (name "unconnected-(IC5-O6-Pad11)") (class "Default")
      (node (ref "IC5") (pin "11") (pinfunction "O6_11") (pintype "open_collector"))
    )
    (net (code "152") (name "unconnected-(IC5-O7-Pad10)") (class "Default")
      (node (ref "IC5") (pin "10") (pinfunction "O7_10") (pintype "open_collector"))
    )
    (net (code "153") (name "unconnected-(MIDI_INA-KL-Pad1)") (class "Default")
      (node (ref "MIDI_IN") (pin "1") (pinfunction "KL_1") (pintype "passive"))
    )
  )
)
